# micro_pogo.net
KiCad netlist of a schematic drawn in EAGLE
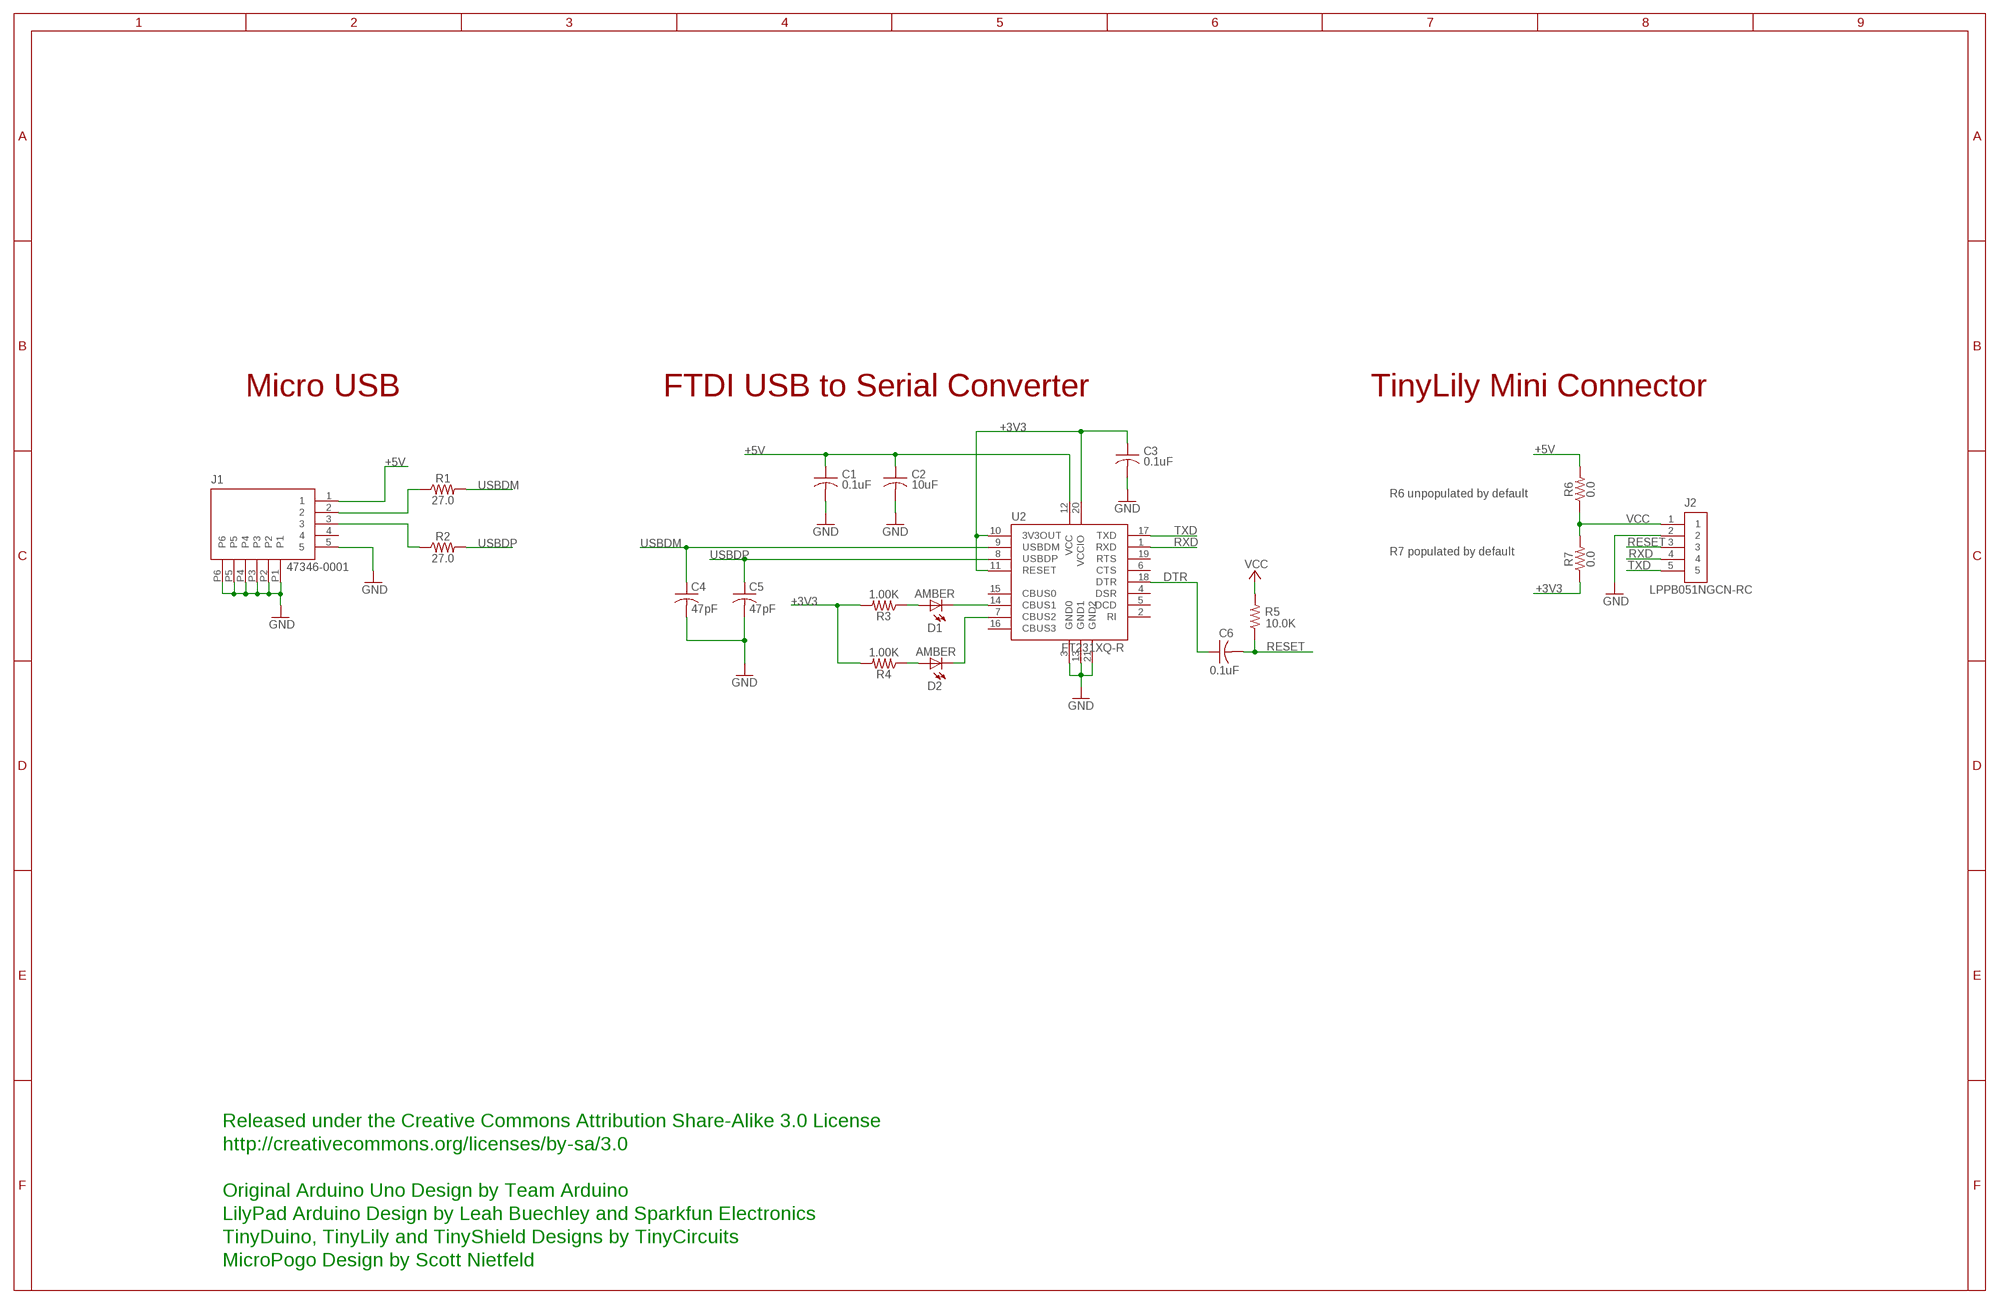
[diagram p0: schematic, sheet 1]

(export (version "E")
  (design (tool "Eeschema 10.0.6"))
  (components
    (comp (ref "C1")
      (value "0.1uF")
      (footprint "eagle-import:C0402")
      (fields (field (name "PARTNO") "AS-ITM-00008"))
      (libsource (lib "eagle-import") (part "AS-ITM-00008"))
    )
    (comp (ref "C2")
      (value "10uF")
      (footprint "eagle-import:C0603")
      (fields (field (name "PARTNO") "AS-ITM-00002"))
      (libsource (lib "eagle-import") (part "AS-ITM-00002"))
    )
    (comp (ref "C3")
      (value "0.1uF")
      (footprint "eagle-import:C0402")
      (fields (field (name "PARTNO") "AS-ITM-00008") (field (name "PARTNO_1") "AS-ITM-00008"))
      (libsource (lib "eagle-import") (part "AS-ITM-00008"))
    )
    (comp (ref "C4")
      (value "47pF")
      (footprint "eagle-import:0402")
      (fields (field (name "PARTNO") "AS-ITM-00241") (field (name "PARTNO_1") "AS-ITM-00241"))
      (libsource (lib "eagle-import") (part "AS-ITM-00241"))
    )
    (comp (ref "C5")
      (value "47pF")
      (footprint "eagle-import:0402")
      (fields (field (name "PARTNO") "AS-ITM-00241") (field (name "PARTNO_1") "AS-ITM-00241"))
      (libsource (lib "eagle-import") (part "AS-ITM-00241"))
    )
    (comp (ref "C6")
      (value "0.1uF")
      (footprint "eagle-import:C0402")
      (fields (field (name "PARTNO") "AS-ITM-00008") (field (name "PARTNO_1") "AS-ITM-00008"))
      (libsource (lib "eagle-import") (part "AS-ITM-00008"))
    )
    (comp (ref "D1")
      (value "AMBER")
      (footprint "eagle-import:LNJ_LED")
      (fields (field (name "PARTNO") "AS-ITM-00026"))
      (libsource (lib "eagle-import") (part "AS-ITM-00026"))
    )
    (comp (ref "D2")
      (value "AMBER")
      (footprint "eagle-import:LNJ_LED")
      (fields (field (name "PARTNO") "AS-ITM-00026"))
      (libsource (lib "eagle-import") (part "AS-ITM-00026"))
    )
    (comp (ref "J1")
      (value "47346-0001")
      (footprint "eagle-import:MICRO_USB")
      (fields (field (name "PARTNO") "AS-ITM-00021") (field (name "PARTNO_1") "AS-ITM-00021"))
      (libsource (lib "eagle-import") (part "AS-ITM-00021"))
    )
    (comp (ref "J2")
      (value "LPPB051NGCN-RC")
      (footprint "eagle-import:1X5_.05_RA_TH_RECPT")
      (fields (field (name "PARTNO") "AS-ITM-00037"))
      (libsource (lib "eagle-import") (part "AS-ITM-00037"))
    )
    (comp (ref "R1")
      (value "27.0")
      (footprint "eagle-import:0402")
      (libsource (lib "eagle-import") (part "AS-ITM-00240"))
    )
    (comp (ref "R2")
      (value "27.0")
      (footprint "eagle-import:0402")
      (libsource (lib "eagle-import") (part "AS-ITM-00240"))
    )
    (comp (ref "R3")
      (value "1.00K")
      (footprint "eagle-import:0402")
      (fields (field (name "PARTNO") "AS-ITM-00003"))
      (libsource (lib "eagle-import") (part "AS-ITM-00003"))
    )
    (comp (ref "R4")
      (value "1.00K")
      (footprint "eagle-import:0402")
      (fields (field (name "PARTNO") "AS-ITM-00003"))
      (libsource (lib "eagle-import") (part "AS-ITM-00003"))
    )
    (comp (ref "R5")
      (value "10.0K")
      (footprint "eagle-import:0402")
      (fields (field (name "PARTNO") "AS-ITM-00032"))
      (libsource (lib "eagle-import") (part "AS-ITM-00032"))
    )
    (comp (ref "R6")
      (value "0.0")
      (footprint "eagle-import:0402")
      (fields (field (name "PARTNO") "AS-ITM-00076"))
      (libsource (lib "eagle-import") (part "AS-ITM-00076"))
    )
    (comp (ref "R7")
      (value "0.0")
      (footprint "eagle-import:0402")
      (fields (field (name "PARTNO") "AS-ITM-00076"))
      (libsource (lib "eagle-import") (part "AS-ITM-00076"))
    )
    (comp (ref "U2")
      (value "FT231XQ-R")
      (footprint "eagle-import:QFN20")
      (fields (field (name "PARTNO") "AS-ITM-00223"))
      (libsource (lib "eagle-import") (part "AS-ITM-00223"))
    )
  )
  (nets
    (net (code "1") (name "/+3V3") (class "Default")
      (node (ref "C3") (pin "1") (pinfunction "1_1") (pintype "passive"))
      (node (ref "R3") (pin "2") (pinfunction "2_2") (pintype "passive"))
      (node (ref "R4") (pin "2") (pinfunction "2_2") (pintype "passive"))
      (node (ref "R7") (pin "1") (pinfunction "1_1") (pintype "passive"))
      (node (ref "U2") (pin "10") (pinfunction "3V3OUT_10") (pintype "bidirectional"))
      (node (ref "U2") (pin "11") (pinfunction "RESET_11") (pintype "bidirectional"))
      (node (ref "U2") (pin "20") (pinfunction "VCCIO_20") (pintype "bidirectional"))
    )
    (net (code "2") (name "/+5V") (class "Default")
      (node (ref "C1") (pin "1") (pinfunction "1_1") (pintype "passive"))
      (node (ref "C2") (pin "1") (pinfunction "1_1") (pintype "passive"))
      (node (ref "J1") (pin "1") (pinfunction "1_1") (pintype "bidirectional"))
      (node (ref "R6") (pin "2") (pinfunction "2_2") (pintype "passive"))
      (node (ref "U2") (pin "12") (pinfunction "VCC_12") (pintype "bidirectional"))
    )
    (net (code "3") (name "/DTR") (class "Default")
      (node (ref "C6") (pin "1") (pinfunction "1_1") (pintype "passive"))
      (node (ref "U2") (pin "18") (pinfunction "DTR_18") (pintype "bidirectional"))
    )
    (net (code "4") (name "/RESET") (class "Default")
      (node (ref "C6") (pin "2") (pinfunction "2_2") (pintype "passive"))
      (node (ref "J2") (pin "3") (pinfunction "3_3") (pintype "bidirectional"))
      (node (ref "R5") (pin "1") (pinfunction "1_1") (pintype "passive"))
    )
    (net (code "5") (name "/RXD") (class "Default")
      (node (ref "J2") (pin "4") (pinfunction "4_4") (pintype "bidirectional"))
      (node (ref "U2") (pin "1") (pinfunction "RXD_1") (pintype "bidirectional"))
    )
    (net (code "6") (name "/TXD") (class "Default")
      (node (ref "J2") (pin "5") (pinfunction "5_5") (pintype "bidirectional"))
      (node (ref "U2") (pin "17") (pinfunction "TXD_17") (pintype "bidirectional"))
    )
    (net (code "7") (name "/USBDM") (class "Default")
      (node (ref "C4") (pin "1") (pinfunction "1_1") (pintype "passive"))
      (node (ref "R1") (pin "2") (pinfunction "2_2") (pintype "passive"))
      (node (ref "U2") (pin "9") (pinfunction "USBDM_9") (pintype "bidirectional"))
    )
    (net (code "8") (name "/USBDP") (class "Default")
      (node (ref "C5") (pin "1") (pinfunction "1_1") (pintype "passive"))
      (node (ref "R2") (pin "2") (pinfunction "2_2") (pintype "passive"))
      (node (ref "U2") (pin "8") (pinfunction "USBDP_8") (pintype "bidirectional"))
    )
    (net (code "9") (name "GND") (class "Default")
      (node (ref "C1") (pin "2") (pinfunction "2_2") (pintype "passive"))
      (node (ref "C2") (pin "2") (pinfunction "2_2") (pintype "passive"))
      (node (ref "C3") (pin "2") (pinfunction "2_2") (pintype "passive"))
      (node (ref "C4") (pin "2") (pinfunction "2_2") (pintype "passive"))
      (node (ref "C5") (pin "2") (pinfunction "2_2") (pintype "passive"))
      (node (ref "J1") (pin "5") (pinfunction "5_5") (pintype "bidirectional"))
      (node (ref "J1") (pin "P1") (pinfunction "P1_P1") (pintype "bidirectional"))
      (node (ref "J1") (pin "P2") (pinfunction "P2_P2") (pintype "bidirectional"))
      (node (ref "J1") (pin "P3") (pinfunction "P3_P3") (pintype "bidirectional"))
      (node (ref "J1") (pin "P4") (pinfunction "P4_P4") (pintype "bidirectional"))
      (node (ref "J1") (pin "P5") (pinfunction "P5_P5") (pintype "bidirectional"))
      (node (ref "J1") (pin "P6") (pinfunction "P6_P6") (pintype "bidirectional"))
      (node (ref "J2") (pin "2") (pinfunction "2_2") (pintype "bidirectional"))
      (node (ref "U2") (pin "13") (pinfunction "GND1_13") (pintype "bidirectional"))
      (node (ref "U2") (pin "21") (pinfunction "GND2_21") (pintype "bidirectional"))
      (node (ref "U2") (pin "3") (pinfunction "GND0_3") (pintype "bidirectional"))
    )
    (net (code "10") (name "Net-(D1-PadA)") (class "Default")
      (node (ref "D1") (pin "A") (pinfunction "A_A") (pintype "passive"))
      (node (ref "R3") (pin "1") (pinfunction "1_1") (pintype "passive"))
    )
    (net (code "11") (name "Net-(D2-PadA)") (class "Default")
      (node (ref "D2") (pin "A") (pinfunction "A_A") (pintype "passive"))
      (node (ref "R4") (pin "1") (pinfunction "1_1") (pintype "passive"))
    )
    (net (code "12") (name "Net-(J1-Pad2)") (class "Default")
      (node (ref "J1") (pin "2") (pinfunction "2_2") (pintype "bidirectional"))
      (node (ref "R1") (pin "1") (pinfunction "1_1") (pintype "passive"))
    )
    (net (code "13") (name "Net-(J1-Pad3)") (class "Default")
      (node (ref "J1") (pin "3") (pinfunction "3_3") (pintype "bidirectional"))
      (node (ref "R2") (pin "1") (pinfunction "1_1") (pintype "passive"))
    )
    (net (code "14") (name "Net-(U2-CBUS1)") (class "Default")
      (node (ref "D1") (pin "C") (pinfunction "C_C") (pintype "passive"))
      (node (ref "U2") (pin "14") (pinfunction "CBUS1_14") (pintype "bidirectional"))
    )
    (net (code "15") (name "Net-(U2-CBUS2)") (class "Default")
      (node (ref "D2") (pin "C") (pinfunction "C_C") (pintype "passive"))
      (node (ref "U2") (pin "7") (pinfunction "CBUS2_7") (pintype "bidirectional"))
    )
    (net (code "16") (name "VCC") (class "Default")
      (node (ref "J2") (pin "1") (pinfunction "1_1") (pintype "bidirectional"))
      (node (ref "R5") (pin "2") (pinfunction "2_2") (pintype "passive"))
      (node (ref "R6") (pin "1") (pinfunction "1_1") (pintype "passive"))
      (node (ref "R7") (pin "2") (pinfunction "2_2") (pintype "passive"))
    )
    (net (code "17") (name "unconnected-(J1-Pad4)") (class "Default")
      (node (ref "J1") (pin "4") (pinfunction "4_4") (pintype "bidirectional"))
    )
    (net (code "18") (name "unconnected-(U2-CBUS0-Pad15)") (class "Default")
      (node (ref "U2") (pin "15") (pinfunction "CBUS0_15") (pintype "bidirectional"))
    )
    (net (code "19") (name "unconnected-(U2-CBUS3-Pad16)") (class "Default")
      (node (ref "U2") (pin "16") (pinfunction "CBUS3_16") (pintype "bidirectional"))
    )
    (net (code "20") (name "unconnected-(U2-CTS-Pad6)") (class "Default")
      (node (ref "U2") (pin "6") (pinfunction "CTS_6") (pintype "bidirectional"))
    )
    (net (code "21") (name "unconnected-(U2-DCD-Pad5)") (class "Default")
      (node (ref "U2") (pin "5") (pinfunction "DCD_5") (pintype "bidirectional"))
    )
    (net (code "22") (name "unconnected-(U2-DSR-Pad4)") (class "Default")
      (node (ref "U2") (pin "4") (pinfunction "DSR_4") (pintype "bidirectional"))
    )
    (net (code "23") (name "unconnected-(U2-RI-Pad2)") (class "Default")
      (node (ref "U2") (pin "2") (pinfunction "RI_2") (pintype "bidirectional"))
    )
    (net (code "24") (name "unconnected-(U2-RTS-Pad19)") (class "Default")
      (node (ref "U2") (pin "19") (pinfunction "RTS_19") (pintype "bidirectional"))
    )
  )
)
